# PCB.net
KiCad netlist of a schematic drawn in EasyEDA Pro
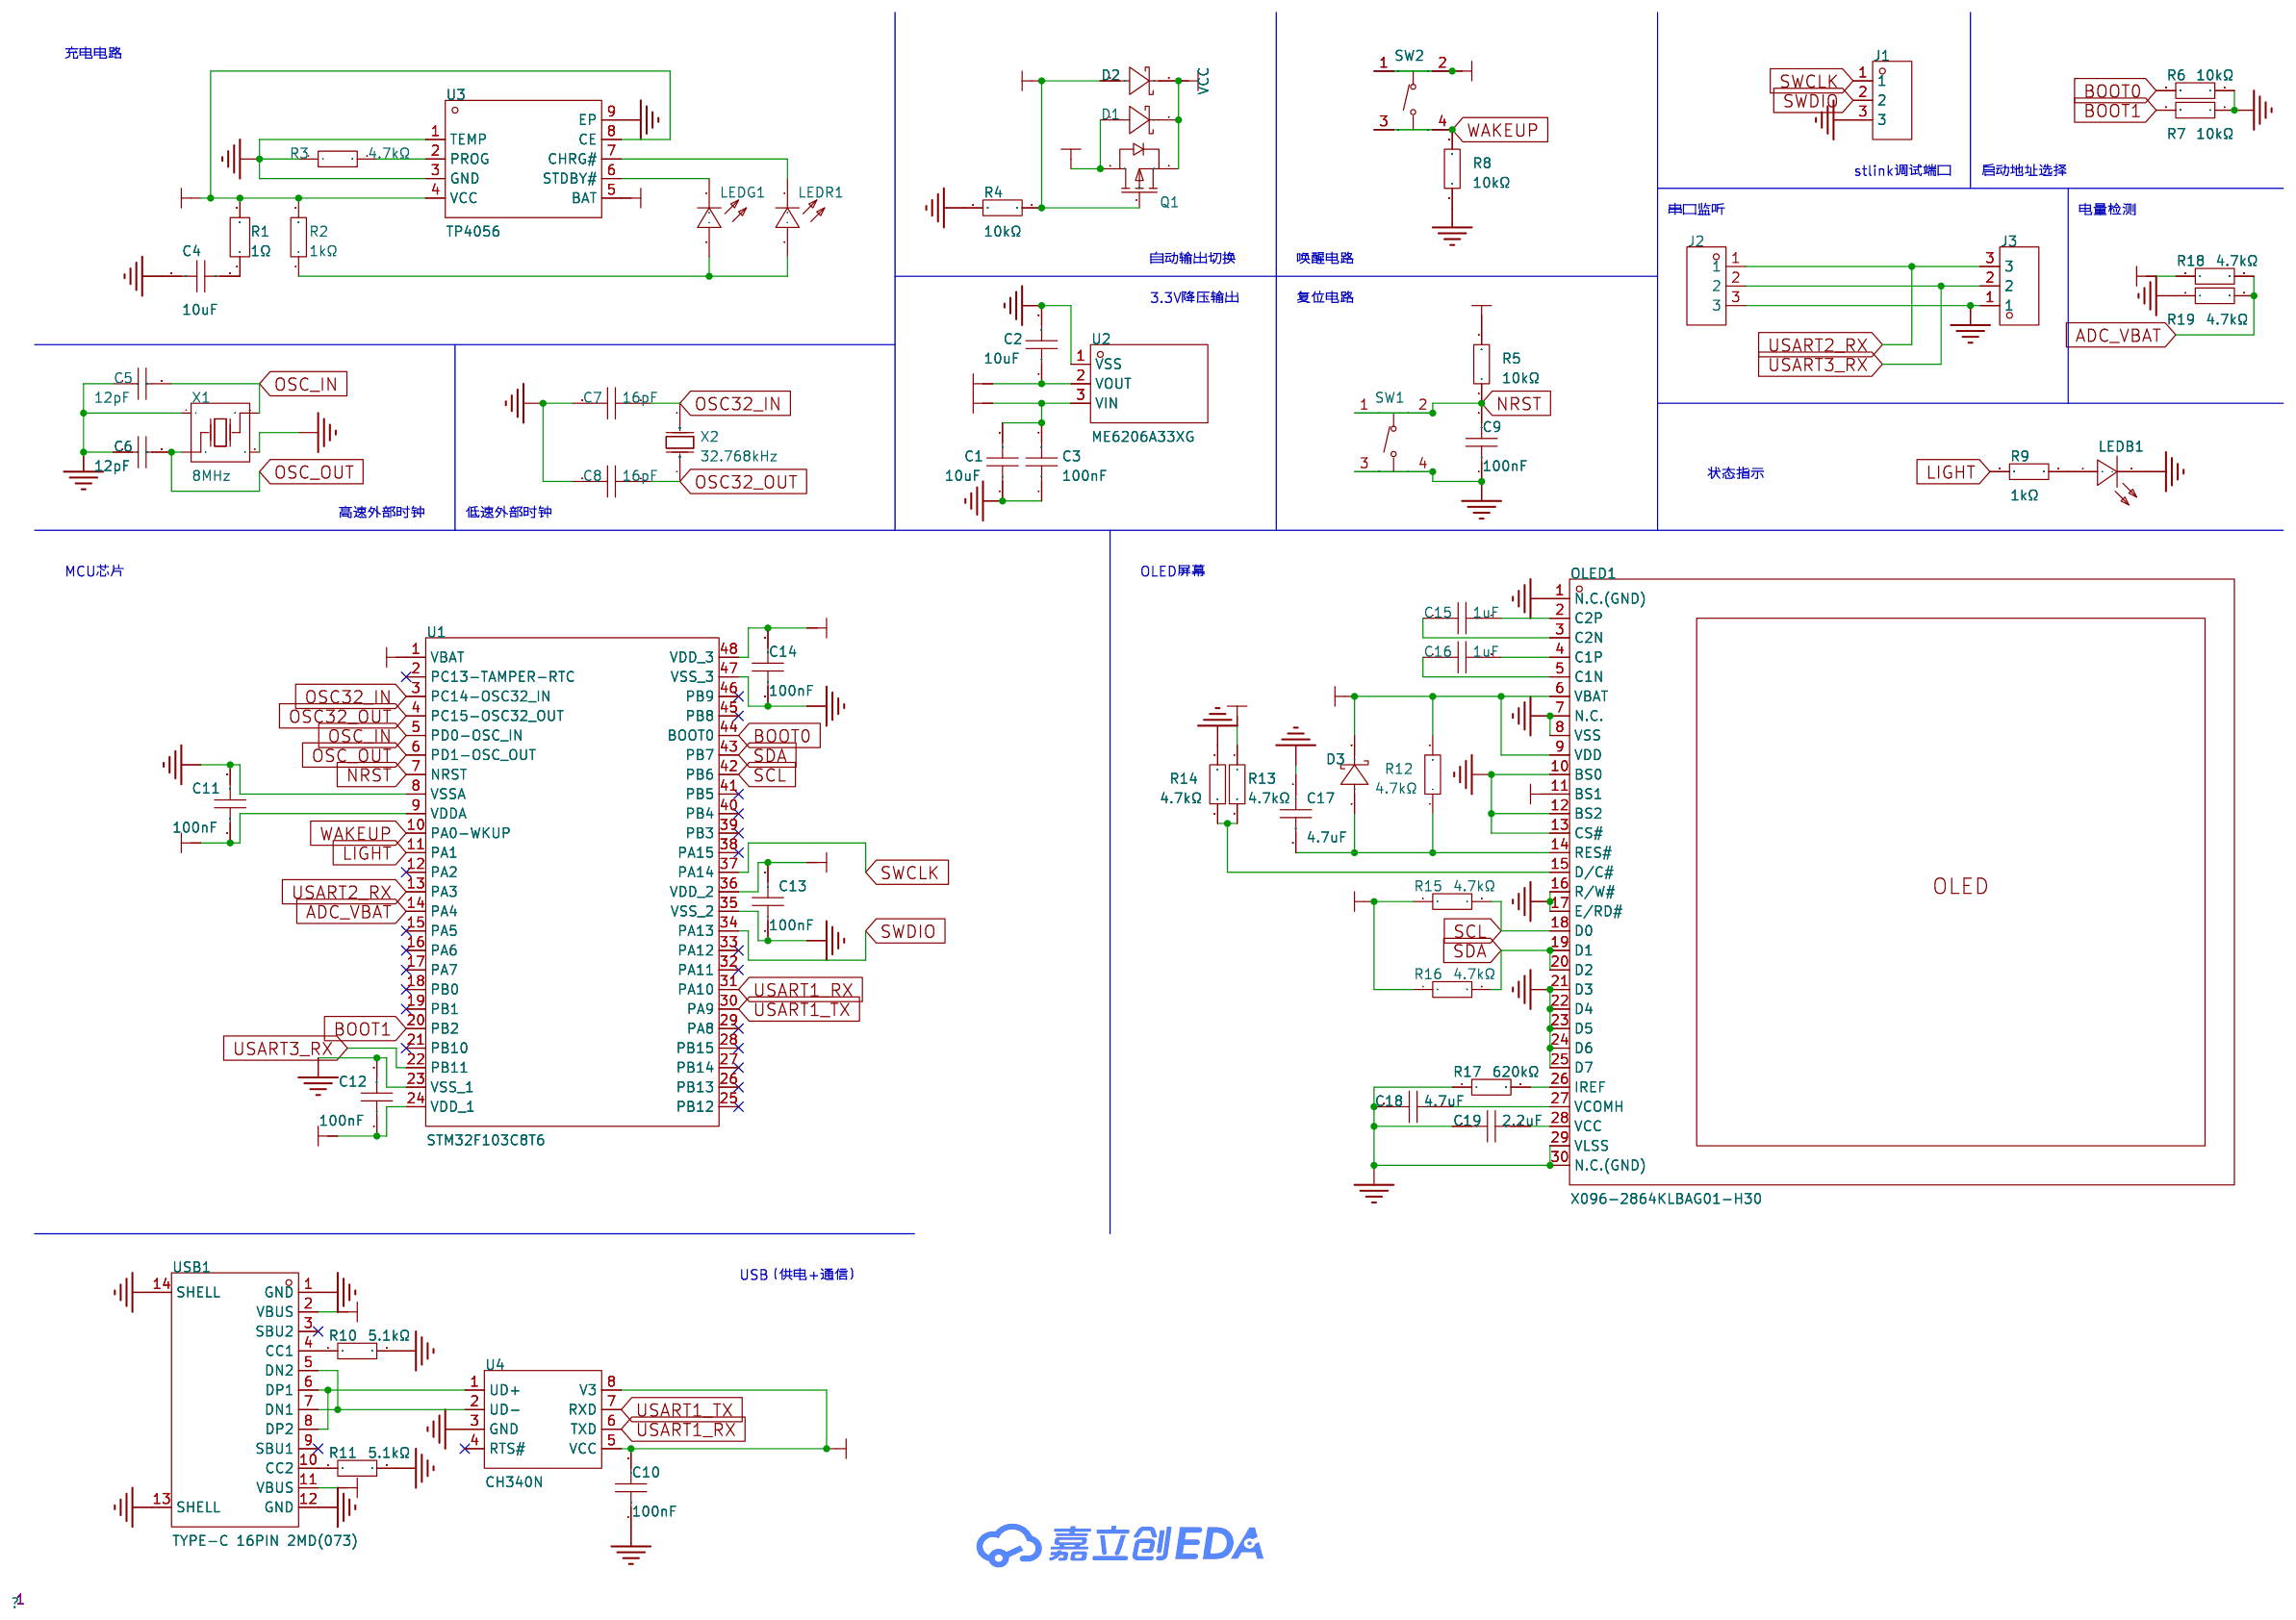
[diagram p0: schematic sheet]

(export (version "E")
  (design (tool "Eeschema 10.0.6"))
  (components
    (comp (ref "C1")
      (value "10uF")
      (footprint "easyedapro:C0603")
      (description "容值:10uF;精度:±10%;额定电压:10V;材质(温度系数):X5R;")
      (fields
        (field (name "Manufacturer Part") "CL10A106KP8NNNC")
        (field (name "Manufacturer") "SAMSUNG(三星)")
      )
      (libsource (lib "easyedapro") (part "CL10A106KP8NNNC"))
    )
    (comp (ref "C2")
      (value "10uF")
      (footprint "easyedapro:C0603")
      (description "容值:10uF;精度:±10%;额定电压:10V;材质(温度系数):X5R;")
      (fields
        (field (name "Manufacturer Part") "CL10A106KP8NNNC")
        (field (name "Manufacturer") "SAMSUNG(三星)")
      )
      (libsource (lib "easyedapro") (part "CL10A106KP8NNNC"))
    )
    (comp (ref "C3")
      (value "100nF")
      (footprint "easyedapro:C0603")
      (description "容值:100nF;精度:±10%;额定电压:50V;温度系数:X7R;")
      (fields
        (field (name "Manufacturer Part") "CGA0603X7R104K500JT")
        (field (name "Manufacturer") "HRE(芯声)")
      )
      (libsource (lib "easyedapro") (part "CGA0603X7R104K500JT"))
    )
    (comp (ref "C4")
      (value "10uF")
      (footprint "easyedapro:C0603")
      (description "容值:10uF;精度:±10%;额定电压:10V;材质(温度系数):X5R;")
      (fields
        (field (name "Manufacturer Part") "CL10A106KP8NNNC")
        (field (name "Manufacturer") "SAMSUNG(三星)")
      )
      (libsource (lib "easyedapro") (part "CL10A106KP8NNNC"))
    )
    (comp (ref "C5")
      (value "12pF")
      (footprint "easyedapro:C0603")
      (description "容值:12pF;精度:±5%;额定电压:50V;材质(温度系数):C0G;")
      (fields
        (field (name "Manufacturer Part") "CL10C120JB8NNNC")
        (field (name "Manufacturer") "SAMSUNG(三星)")
      )
      (libsource (lib "easyedapro") (part "CL10C120JB8NNNC"))
    )
    (comp (ref "C6")
      (value "12pF")
      (footprint "easyedapro:C0603")
      (description "容值:12pF;精度:±5%;额定电压:50V;材质(温度系数):C0G;")
      (fields
        (field (name "Manufacturer Part") "CL10C120JB8NNNC")
        (field (name "Manufacturer") "SAMSUNG(三星)")
      )
      (libsource (lib "easyedapro") (part "CL10C120JB8NNNC"))
    )
    (comp (ref "C7")
      (value "16pF")
      (footprint "easyedapro:C0603")
      (description "容值:16pF;精度:±5%;额定电压:50V;材质(温度系数):NP0;")
      (fields
        (field (name "Manufacturer Part") "CC0603JRNPO9BN160")
        (field (name "Manufacturer") "YAGEO(国巨)")
      )
      (libsource (lib "easyedapro") (part "CC0603JRNPO9BN160"))
    )
    (comp (ref "C8")
      (value "16pF")
      (footprint "easyedapro:C0603")
      (description "容值:16pF;精度:±5%;额定电压:50V;材质(温度系数):NP0;")
      (fields
        (field (name "Manufacturer Part") "CC0603JRNPO9BN160")
        (field (name "Manufacturer") "YAGEO(国巨)")
      )
      (libsource (lib "easyedapro") (part "CC0603JRNPO9BN160"))
    )
    (comp (ref "C9")
      (value "100nF")
      (footprint "easyedapro:C0603")
      (description "容值:100nF;精度:±10%;额定电压:50V;温度系数:X7R;")
      (fields
        (field (name "Manufacturer Part") "CGA0603X7R104K500JT")
        (field (name "Manufacturer") "HRE(芯声)")
      )
      (libsource (lib "easyedapro") (part "CGA0603X7R104K500JT"))
    )
    (comp (ref "C10")
      (value "100nF")
      (footprint "easyedapro:C0603")
      (description "容值:100nF;精度:±10%;额定电压:50V;温度系数:X7R;")
      (fields
        (field (name "Manufacturer Part") "CGA0603X7R104K500JT")
        (field (name "Manufacturer") "HRE(芯声)")
      )
      (libsource (lib "easyedapro") (part "CGA0603X7R104K500JT"))
    )
    (comp (ref "C11")
      (value "100nF")
      (footprint "easyedapro:C0603")
      (description "容值:100nF;精度:±10%;额定电压:50V;温度系数:X7R;")
      (fields
        (field (name "Manufacturer Part") "CGA0603X7R104K500JT")
        (field (name "Manufacturer") "HRE(芯声)")
      )
      (libsource (lib "easyedapro") (part "CGA0603X7R104K500JT"))
    )
    (comp (ref "C12")
      (value "100nF")
      (footprint "easyedapro:C0603")
      (description "容值:100nF;精度:±10%;额定电压:50V;温度系数:X7R;")
      (fields
        (field (name "Manufacturer Part") "CGA0603X7R104K500JT")
        (field (name "Manufacturer") "HRE(芯声)")
      )
      (libsource (lib "easyedapro") (part "CGA0603X7R104K500JT"))
    )
    (comp (ref "C13")
      (value "100nF")
      (footprint "easyedapro:C0603")
      (description "容值:100nF;精度:±10%;额定电压:50V;温度系数:X7R;")
      (fields
        (field (name "Manufacturer Part") "CGA0603X7R104K500JT")
        (field (name "Manufacturer") "HRE(芯声)")
      )
      (libsource (lib "easyedapro") (part "CGA0603X7R104K500JT"))
    )
    (comp (ref "C14")
      (value "100nF")
      (footprint "easyedapro:C0603")
      (description "容值:100nF;精度:±10%;额定电压:50V;温度系数:X7R;")
      (fields
        (field (name "Manufacturer Part") "CGA0603X7R104K500JT")
        (field (name "Manufacturer") "HRE(芯声)")
      )
      (libsource (lib "easyedapro") (part "CGA0603X7R104K500JT"))
    )
    (comp (ref "C15")
      (value "1uF")
      (footprint "easyedapro:C0603")
      (description "容值:1uF;精度:±10%;额定电压:50V;材质(温度系数):X5R;")
      (fields
        (field (name "Manufacturer Part") "CL10A105KB8NNNC")
        (field (name "Manufacturer") "SAMSUNG(三星)")
      )
      (libsource (lib "easyedapro") (part "CL10A105KB8NNNC"))
    )
    (comp (ref "C16")
      (value "1uF")
      (footprint "easyedapro:C0603")
      (description "容值:1uF;精度:±10%;额定电压:50V;材质(温度系数):X5R;")
      (fields
        (field (name "Manufacturer Part") "CL10A105KB8NNNC")
        (field (name "Manufacturer") "SAMSUNG(三星)")
      )
      (libsource (lib "easyedapro") (part "CL10A105KB8NNNC"))
    )
    (comp (ref "C17")
      (value "4.7uF")
      (footprint "easyedapro:C0603")
      (description "容值:4.7uF;精度:±10%;额定电压:16V;材质(温度系数):X5R;")
      (fields
        (field (name "Manufacturer Part") "CL10A475KO8NNNC")
        (field (name "Manufacturer") "SAMSUNG(三星)")
      )
      (libsource (lib "easyedapro") (part "CL10A475KO8NNNC"))
    )
    (comp (ref "C18")
      (value "4.7uF")
      (footprint "easyedapro:C0603")
      (description "容值:4.7uF;精度:±10%;额定电压:16V;材质(温度系数):X5R;")
      (fields
        (field (name "Manufacturer Part") "CL10A475KO8NNNC")
        (field (name "Manufacturer") "SAMSUNG(三星)")
      )
      (libsource (lib "easyedapro") (part "CL10A475KO8NNNC"))
    )
    (comp (ref "C19")
      (value "2.2uF")
      (footprint "easyedapro:C0603")
      (description "容值:2.2uF;精度:±10%;额定电压:50V;材质(温度系数):X5R;")
      (fields
        (field (name "Manufacturer Part") "CL10A225KB8NNNC")
        (field (name "Manufacturer") "SAMSUNG(三星)")
      )
      (libsource (lib "easyedapro") (part "CL10A225KB8NNNC"))
    )
    (comp (ref "D1")
      (value "DSK14")
      (footprint "easyedapro:SOD-123_L2.8-W1.8-LS3.7-FD")
      (description "二极管配置:-;正向压降(Vf):550mV@1A;直流反向耐压(Vr):40V;平均整流电流(Io):1A;")
      (fields (field (name "Manufacturer") "FUXINSEMI(富芯森美)"))
      (libsource (lib "easyedapro") (part "DSK14_C908228"))
    )
    (comp (ref "D2")
      (value "DSK14")
      (footprint "easyedapro:SOD-123_L2.8-W1.8-LS3.7-FD")
      (description "二极管配置:-;正向压降(Vf):550mV@1A;直流反向耐压(Vr):40V;平均整流电流(Io):1A;")
      (fields (field (name "Manufacturer") "FUXINSEMI(富芯森美)"))
      (libsource (lib "easyedapro") (part "DSK14_C908228"))
    )
    (comp (ref "D3")
      (value "DSK14")
      (footprint "easyedapro:SOD-123_L2.8-W1.8-LS3.7-FD")
      (description "二极管配置:-;正向压降(Vf):550mV@1A;直流反向耐压(Vr):40V;平均整流电流(Io):1A;")
      (fields (field (name "Manufacturer") "FUXINSEMI(富芯森美)"))
      (libsource (lib "easyedapro") (part "DSK14_C908228"))
    )
    (comp (ref "J1")
      (value "X6511FRS-03-C85D30")
      (footprint "easyedapro:HDR-SMD_3P-P2.54-H-F-L11.5")
      (description "插孔结构:1x3P;间距:2.54mm;安装类型:卧贴;排数:单排;总孔位数:3P;塑高:8.5mm;")
      (fields (field (name "Manufacturer") "XKB Connectivity(中国星坤)"))
      (libsource (lib "easyedapro") (part "X6511FRS-03-C85D30"))
    )
    (comp (ref "J2")
      (value "X6511FRS-03-C85D30")
      (footprint "easyedapro:HDR-SMD_3P-P2.54-H-F-L11.5")
      (description "插孔结构:1x3P;间距:2.54mm;安装类型:卧贴;排数:单排;总孔位数:3P;塑高:8.5mm;")
      (fields (field (name "Manufacturer") "XKB Connectivity(中国星坤)"))
      (libsource (lib "easyedapro") (part "X6511FRS-03-C85D30"))
    )
    (comp (ref "J3")
      (value "X6511FRS-03-C85D30")
      (footprint "easyedapro:HDR-SMD_3P-P2.54-H-F-L11.5")
      (description "插孔结构:1x3P;间距:2.54mm;安装类型:卧贴;排数:单排;总孔位数:3P;塑高:8.5mm;")
      (fields (field (name "Manufacturer") "XKB Connectivity(中国星坤)"))
      (libsource (lib "easyedapro") (part "X6511FRS-03-C85D30"))
    )
    (comp (ref "LEDB1")
      (value "NCD0805B2")
      (footprint "easyedapro:LED0805-R-RD")
      (fields (field (name "Manufacturer") "国星光电"))
      (libsource (lib "easyedapro") (part "FC-A2012BK-470H2"))
    )
    (comp (ref "LEDG1")
      (value "NCD0603G1")
      (footprint "easyedapro:LED0603-RD_1")
      (fields (field (name "Manufacturer") "国星光电"))
      (libsource (lib "easyedapro") (part "FC-D1608UGK-520D10"))
    )
    (comp (ref "LEDR1")
      (value "NCD0603R1")
      (footprint "easyedapro:LED0603-RD_RED")
      (fields (field (name "Manufacturer") "国星光电"))
      (libsource (lib "easyedapro") (part "FC-DA1608HRK-620D"))
    )
    (comp (ref "OLED1")
      (value "X096-2864KLBAG01-H30")
      (footprint "easyedapro:OLED-SMD_X096-2864KLBAG01-H30")
      (description "主控芯片:SSD1315;尺寸(inch):0.96;像素分辨率:128x64;")
      (fields (field (name "Manufacturer") "Newvision(新智景)"))
      (libsource (lib "easyedapro") (part "X096-2864KLBAG01-H30"))
    )
    (comp (ref "Q1")
      (value "SI2301S")
      (footprint "easyedapro:SOT-23-3_L2.9-W1.3-P0.95-LS2.4-BR")
      (description "类型:-;漏源电压(Vdss):20V;连续漏极电流(Id):2.3A;导通电阻(RDS(on)):142mΩ@2.5V,2A;耗散功率(Pd):-;阈值电压(Vgs(th)):400mV;")
      (fields (field (name "Manufacturer") "GOODWORK(固得沃克)"))
      (libsource (lib "easyedapro") (part "SI2301S_C18186231"))
    )
    (comp (ref "R1")
      (value "1Ω")
      (footprint "easyedapro:R0603")
      (description "电阻类型:厚膜电阻;阻值:1Ω;精度:±5%;功率:100mW;最大工作电压:75V;温度系数:±200ppm/°C;")
      (fields (field (name "Manufacturer Part") "FRC0603J1R0 TS") (field (name "Manufacturer") "FOJAN(富捷)"))
      (libsource (lib "easyedapro") (part "FRC0603J1R0 TS"))
    )
    (comp (ref "R2")
      (value "1kΩ")
      (footprint "easyedapro:R0603")
      (description "电阻类型:厚膜电阻;阻值:1kΩ;精度:±1%;功率:100mW;最大工作电压:75V;温度系数:±100ppm/°C;")
      (fields
        (field (name "Manufacturer Part") "0603WAF1001T5E")
        (field (name "Manufacturer") "UNI-ROYAL(厚声)")
      )
      (libsource (lib "easyedapro") (part "0603WAF1001T5E"))
    )
    (comp (ref "R3")
      (value "4.7kΩ")
      (footprint "easyedapro:R0603")
      (description "电阻类型:厚膜电阻;阻值:4.7kΩ;精度:±1%;功率:100mW;最大工作电压:75V;温度系数:±100ppm/°C;")
      (fields
        (field (name "Manufacturer Part") "0603WAF4701T5E")
        (field (name "Manufacturer") "UNI-ROYAL(厚声)")
      )
      (libsource (lib "easyedapro") (part "0603WAF4701T5E"))
    )
    (comp (ref "R4")
      (value "10kΩ")
      (footprint "easyedapro:R0603")
      (description "电阻类型:厚膜电阻;阻值:10kΩ;精度:±1%;功率:100mW;最大工作电压:75V;温度系数:±100ppm/°C;")
      (fields
        (field (name "Manufacturer Part") "0603WAF1002T5E")
        (field (name "Manufacturer") "UNI-ROYAL(厚声)")
      )
      (libsource (lib "easyedapro") (part "0603WAF1002T5E"))
    )
    (comp (ref "R5")
      (value "10kΩ")
      (footprint "easyedapro:R0603")
      (description "电阻类型:厚膜电阻;阻值:10kΩ;精度:±1%;功率:100mW;最大工作电压:75V;温度系数:±100ppm/°C;")
      (fields
        (field (name "Manufacturer Part") "0603WAF1002T5E")
        (field (name "Manufacturer") "UNI-ROYAL(厚声)")
      )
      (libsource (lib "easyedapro") (part "0603WAF1002T5E"))
    )
    (comp (ref "R6")
      (value "10kΩ")
      (footprint "easyedapro:R0603")
      (description "电阻类型:厚膜电阻;阻值:10kΩ;精度:±1%;功率:100mW;最大工作电压:75V;温度系数:±100ppm/°C;")
      (fields
        (field (name "Manufacturer Part") "0603WAF1002T5E")
        (field (name "Manufacturer") "UNI-ROYAL(厚声)")
      )
      (libsource (lib "easyedapro") (part "0603WAF1002T5E"))
    )
    (comp (ref "R7")
      (value "10kΩ")
      (footprint "easyedapro:R0603")
      (description "电阻类型:厚膜电阻;阻值:10kΩ;精度:±1%;功率:100mW;最大工作电压:75V;温度系数:±100ppm/°C;")
      (fields
        (field (name "Manufacturer Part") "0603WAF1002T5E")
        (field (name "Manufacturer") "UNI-ROYAL(厚声)")
      )
      (libsource (lib "easyedapro") (part "0603WAF1002T5E"))
    )
    (comp (ref "R8")
      (value "10kΩ")
      (footprint "easyedapro:R0603")
      (description "电阻类型:厚膜电阻;阻值:10kΩ;精度:±1%;功率:100mW;最大工作电压:75V;温度系数:±100ppm/°C;")
      (fields
        (field (name "Manufacturer Part") "0603WAF1002T5E")
        (field (name "Manufacturer") "UNI-ROYAL(厚声)")
      )
      (libsource (lib "easyedapro") (part "0603WAF1002T5E"))
    )
    (comp (ref "R9")
      (value "1kΩ")
      (footprint "easyedapro:R0603")
      (description "电阻类型:厚膜电阻;阻值:1kΩ;精度:±1%;功率:100mW;最大工作电压:75V;温度系数:±100ppm/°C;")
      (fields
        (field (name "Manufacturer Part") "0603WAF1001T5E")
        (field (name "Manufacturer") "UNI-ROYAL(厚声)")
      )
      (libsource (lib "easyedapro") (part "0603WAF1001T5E"))
    )
    (comp (ref "R10")
      (value "5.1kΩ")
      (footprint "easyedapro:R0603")
      (description "阻值:5.1kΩ;精度:±1%;功率:100mW;")
      (fields (field (name "Manufacturer Part") "ETCR0603F5K10K9") (field (name "Manufacturer") "RESI(开步睿思)"))
      (libsource (lib "easyedapro") (part "ETCR0603F5K10K9"))
    )
    (comp (ref "R11")
      (value "5.1kΩ")
      (footprint "easyedapro:R0603")
      (description "阻值:5.1kΩ;精度:±1%;功率:100mW;")
      (fields (field (name "Manufacturer Part") "ETCR0603F5K10K9") (field (name "Manufacturer") "RESI(开步睿思)"))
      (libsource (lib "easyedapro") (part "ETCR0603F5K10K9"))
    )
    (comp (ref "R12")
      (value "4.7kΩ")
      (footprint "easyedapro:R0603")
      (description "电阻类型:厚膜电阻;阻值:4.7kΩ;精度:±1%;功率:100mW;最大工作电压:75V;温度系数:±100ppm/°C;")
      (fields
        (field (name "Manufacturer Part") "0603WAF4701T5E")
        (field (name "Manufacturer") "UNI-ROYAL(厚声)")
      )
      (libsource (lib "easyedapro") (part "0603WAF4701T5E"))
    )
    (comp (ref "R13")
      (value "4.7kΩ")
      (footprint "easyedapro:R0603")
      (description "电阻类型:厚膜电阻;阻值:4.7kΩ;精度:±1%;功率:100mW;最大工作电压:75V;温度系数:±100ppm/°C;")
      (fields
        (field (name "Manufacturer Part") "0603WAF4701T5E")
        (field (name "Manufacturer") "UNI-ROYAL(厚声)")
      )
      (libsource (lib "easyedapro") (part "0603WAF4701T5E"))
    )
    (comp (ref "R14")
      (value "4.7kΩ")
      (footprint "easyedapro:R0603")
      (description "电阻类型:厚膜电阻;阻值:4.7kΩ;精度:±1%;功率:100mW;最大工作电压:75V;温度系数:±100ppm/°C;")
      (fields
        (field (name "Manufacturer Part") "0603WAF4701T5E")
        (field (name "Manufacturer") "UNI-ROYAL(厚声)")
      )
      (libsource (lib "easyedapro") (part "0603WAF4701T5E"))
    )
    (comp (ref "R15")
      (value "4.7kΩ")
      (footprint "easyedapro:R0603")
      (description "电阻类型:厚膜电阻;阻值:4.7kΩ;精度:±1%;功率:100mW;最大工作电压:75V;温度系数:±100ppm/°C;")
      (fields
        (field (name "Manufacturer Part") "0603WAF4701T5E")
        (field (name "Manufacturer") "UNI-ROYAL(厚声)")
      )
      (libsource (lib "easyedapro") (part "0603WAF4701T5E"))
    )
    (comp (ref "R16")
      (value "4.7kΩ")
      (footprint "easyedapro:R0603")
      (description "电阻类型:厚膜电阻;阻值:4.7kΩ;精度:±1%;功率:100mW;最大工作电压:75V;温度系数:±100ppm/°C;")
      (fields
        (field (name "Manufacturer Part") "0603WAF4701T5E")
        (field (name "Manufacturer") "UNI-ROYAL(厚声)")
      )
      (libsource (lib "easyedapro") (part "0603WAF4701T5E"))
    )
    (comp (ref "R17")
      (value "620kΩ")
      (footprint "easyedapro:R0603")
      (description "电阻类型:厚膜电阻;阻值:620kΩ;精度:±1%;功率:100mW;最大工作电压:75V;温度系数:±100ppm/°C;")
      (fields
        (field (name "Manufacturer Part") "0603WAF6203T5E")
        (field (name "Manufacturer") "UNI-ROYAL(厚声)")
      )
      (libsource (lib "easyedapro") (part "0603WAF6203T5E"))
    )
    (comp (ref "R18")
      (value "4.7kΩ")
      (footprint "easyedapro:R0603")
      (description "电阻类型:厚膜电阻;阻值:4.7kΩ;精度:±1%;功率:100mW;最大工作电压:75V;温度系数:±100ppm/°C;")
      (fields
        (field (name "Manufacturer Part") "0603WAF4701T5E")
        (field (name "Manufacturer") "UNI-ROYAL(厚声)")
      )
      (libsource (lib "easyedapro") (part "0603WAF4701T5E"))
    )
    (comp (ref "R19")
      (value "4.7kΩ")
      (footprint "easyedapro:R0603")
      (description "电阻类型:厚膜电阻;阻值:4.7kΩ;精度:±1%;功率:100mW;最大工作电压:75V;温度系数:±100ppm/°C;")
      (fields
        (field (name "Manufacturer Part") "0603WAF4701T5E")
        (field (name "Manufacturer") "UNI-ROYAL(厚声)")
      )
      (libsource (lib "easyedapro") (part "0603WAF4701T5E"))
    )
    (comp (ref "SW1")
      (value "TS-1187A-B-A-B")
      (footprint "easyedapro:SW-SMD_4P-L5.1-W5.1-P3.70-LS6.5-TL_H1.5")
      (fields (field (name "Manufacturer") "XKB Connectivity(中国星坤)"))
      (libsource (lib "easyedapro") (part "TS-1187A-B-A-B"))
    )
    (comp (ref "SW2")
      (value "TS-1187A-B-A-B")
      (footprint "easyedapro:SW-SMD_4P-L5.1-W5.1-P3.70-LS6.5-TL_H1.5")
      (fields (field (name "Manufacturer") "XKB Connectivity(中国星坤)"))
      (libsource (lib "easyedapro") (part "TS-1187A-B-A-B"))
    )
    (comp (ref "U1")
      (value "STM32F103C8T6")
      (footprint "easyedapro:LQFP-48_L7.0-W7.0-P0.50-LS9.0-BL")
      (description "CPU内核:ARM-M3;CPU最大主频:72MHz;应用领域:-;")
      (fields (field (name "Manufacturer") "ST(意法半导体)"))
      (libsource (lib "easyedapro") (part "STM32F103C8T6"))
    )
    (comp (ref "U2")
      (value "ME6206A33XG")
      (footprint "easyedapro:SOT-23-3_L2.9-W1.6-P1.90-LS2.8-BR")
      (description "输出类型:固定;最大输入电压:6V;输出电压:3.3V;最大输出电流:300mA;电源纹波抑制比(PSRR):50dB@(1kHz);输出极性:正极;")
      (fields (field (name "Manufacturer") "MICRONE(南京微盟)"))
      (libsource (lib "easyedapro") (part "ME6206A33XG"))
    )
    (comp (ref "U3")
      (value "TP4056")
      (footprint "easyedapro:ESOP-8_L4.9-W3.9-P1.27-LS6.0-BL-EP")
      (description "工作电压:4V~6V;最大充电电流:1A;电池类型:锂离子/聚合物;电池节数:1;")
      (fields (field (name "Manufacturer") "TPOWER(天源)"))
      (libsource (lib "easyedapro") (part "TP4056_C382139"))
    )
    (comp (ref "U4")
      (value "CH340N")
      (footprint "easyedapro:SOP-8_L4.9-W3.9-P1.27-LS6.0-BL")
      (description "应用功能:USB转串口;接口协议:USB 2.0;通道数:1;数据速率:2Mbps;")
      (fields (field (name "Manufacturer") "WCH(南京沁恒)"))
      (libsource (lib "easyedapro") (part "CH340N_C2977777"))
    )
    (comp (ref "USB1")
      (value "TYPE-C 16PIN 2MD(073)")
      (footprint "easyedapro:USB-C-SMD_TYPE-C-6PIN-2MD-073")
      (description "连接器类型:Type-C;标准:USB 3.1;公母:母;安装方式:卧贴;触点数量:16P;端口数量:1;额定电流 - 电源:5A;工作温度范围:-25°C~+85°C;")
      (fields (field (name "Manufacturer") "SHOU HAN(首韩)"))
      (libsource (lib "easyedapro") (part "TYPE-C 16PIN 2MD(073)"))
    )
    (comp (ref "X1")
      (value "8MHz")
      (footprint "easyedapro:CRYSTAL-SMD_4P-L3.2-W2.5-BL")
      (description "晶振类型:贴片晶振;频率:8MHz;常温频差:±10ppm;负载电容:10pF;频率稳定度:±15ppm;")
      (fields (field (name "Manufacturer Part") "TAXM8M4RDBCCT2T") (field (name "Manufacturer") "YJX(雅晶鑫)"))
      (libsource (lib "easyedapro") (part "TAXM8M4RDBCCT2T"))
    )
    (comp (ref "X2")
      (value "32.768kHz")
      (footprint "easyedapro:CRYSTAL-SMD_L3.2-W1.5-1")
      (description "晶振类型:贴片晶振;频率:32.768kHz;常温频差:±20ppm;负载电容:12.5pF;频率稳定度:±30ppm;")
      (fields
        (field (name "Manufacturer Part") "XKXGI-SUA-32.768K")
        (field (name "Manufacturer") "YXC(扬兴晶振)")
      )
      (libsource (lib "easyedapro") (part "XKXGI-SUA-32.768K"))
    )
  )
  (nets
    (net (code "1") (name "3V3") (class "Default")
      (node (ref "C10") (pin "2") (pinfunction "2_2") (pintype "unspecified"))
      (node (ref "C11") (pin "1") (pinfunction "1_1") (pintype "unspecified"))
      (node (ref "C12") (pin "1") (pinfunction "1_1") (pintype "unspecified"))
      (node (ref "C13") (pin "2") (pinfunction "2_2") (pintype "unspecified"))
      (node (ref "C14") (pin "2") (pinfunction "2_2") (pintype "unspecified"))
      (node (ref "C2") (pin "1") (pinfunction "1_1") (pintype "unspecified"))
      (node (ref "D3") (pin "2") (pinfunction "K_2") (pintype "unspecified"))
      (node (ref "OLED1") (pin "11") (pinfunction "BS1_11") (pintype "unspecified"))
      (node (ref "OLED1") (pin "6") (pinfunction "VBAT_6") (pintype "unspecified"))
      (node (ref "OLED1") (pin "9") (pinfunction "VDD_9") (pintype "unspecified"))
      (node (ref "R12") (pin "2") (pinfunction "2_2") (pintype "input"))
      (node (ref "R13") (pin "1") (pinfunction "1_1") (pintype "input"))
      (node (ref "R15") (pin "1") (pinfunction "1_1") (pintype "input"))
      (node (ref "R16") (pin "1") (pinfunction "1_1") (pintype "input"))
      (node (ref "R5") (pin "2") (pinfunction "2_2") (pintype "input"))
      (node (ref "SW2") (pin "1") (pinfunction "A_1") (pintype "unspecified"))
      (node (ref "SW2") (pin "2") (pinfunction "B_2") (pintype "unspecified"))
      (node (ref "U1") (pin "1") (pinfunction "VBAT_1") (pintype "unspecified"))
      (node (ref "U1") (pin "24") (pinfunction "VDD_1_24") (pintype "unspecified"))
      (node (ref "U1") (pin "36") (pinfunction "VDD_2_36") (pintype "unspecified"))
      (node (ref "U1") (pin "48") (pinfunction "VDD_3_48") (pintype "unspecified"))
      (node (ref "U1") (pin "9") (pinfunction "VDDA_9") (pintype "unspecified"))
      (node (ref "U2") (pin "2") (pinfunction "VOUT_2") (pintype "unspecified"))
      (node (ref "U4") (pin "5") (pinfunction "VCC_5") (pintype "unspecified"))
      (node (ref "U4") (pin "8") (pinfunction "V3_8") (pintype "unspecified"))
    )
    (net (code "2") (name "5V") (class "Default")
      (node (ref "D2") (pin "1") (pinfunction "A_1") (pintype "unspecified"))
      (node (ref "Q1") (pin "1") (pinfunction "G_1") (pintype "unspecified"))
      (node (ref "R1") (pin "2") (pinfunction "2_2") (pintype "unspecified"))
      (node (ref "R2") (pin "2") (pinfunction "2_2") (pintype "input"))
      (node (ref "R4") (pin "1") (pinfunction "1_1") (pintype "input"))
      (node (ref "U3") (pin "4") (pinfunction "VCC_4") (pintype "unspecified"))
      (node (ref "U3") (pin "8") (pinfunction "CE_8") (pintype "unspecified"))
      (node (ref "USB1") (pin "11") (pinfunction "VBUS_11") (pintype "unspecified"))
      (node (ref "USB1") (pin "2") (pinfunction "VBUS_2") (pintype "unspecified"))
    )
    (net (code "3") (name "ADC_VBAT") (class "Default")
      (node (ref "R18") (pin "2") (pinfunction "2_2") (pintype "input"))
      (node (ref "R19") (pin "2") (pinfunction "2_2") (pintype "input"))
      (node (ref "U1") (pin "14") (pinfunction "PA4_14") (pintype "unspecified"))
    )
    (net (code "4") (name "BOOT0") (class "Default")
      (node (ref "R6") (pin "2") (pinfunction "2_2") (pintype "input"))
      (node (ref "U1") (pin "44") (pinfunction "BOOT0_44") (pintype "unspecified"))
    )
    (net (code "5") (name "BOOT1") (class "Default")
      (node (ref "R7") (pin "2") (pinfunction "2_2") (pintype "input"))
      (node (ref "U1") (pin "20") (pinfunction "PB2_20") (pintype "unspecified"))
    )
    (net (code "6") (name "GND") (class "Default")
      (node (ref "C1") (pin "1") (pinfunction "1_1") (pintype "unspecified"))
      (node (ref "C10") (pin "1") (pinfunction "1_1") (pintype "unspecified"))
      (node (ref "C11") (pin "2") (pinfunction "2_2") (pintype "unspecified"))
      (node (ref "C12") (pin "2") (pinfunction "2_2") (pintype "unspecified"))
      (node (ref "C13") (pin "1") (pinfunction "1_1") (pintype "unspecified"))
      (node (ref "C14") (pin "1") (pinfunction "1_1") (pintype "unspecified"))
      (node (ref "C17") (pin "1") (pinfunction "1_1") (pintype "unspecified"))
      (node (ref "C18") (pin "2") (pinfunction "2_2") (pintype "unspecified"))
      (node (ref "C19") (pin "1") (pinfunction "1_1") (pintype "unspecified"))
      (node (ref "C2") (pin "2") (pinfunction "2_2") (pintype "unspecified"))
      (node (ref "C3") (pin "1") (pinfunction "1_1") (pintype "unspecified"))
      (node (ref "C4") (pin "2") (pinfunction "2_2") (pintype "unspecified"))
      (node (ref "C5") (pin "1") (pinfunction "1_1") (pintype "input"))
      (node (ref "C6") (pin "1") (pinfunction "1_1") (pintype "input"))
      (node (ref "C7") (pin "2") (pinfunction "2_2") (pintype "unspecified"))
      (node (ref "C8") (pin "2") (pinfunction "2_2") (pintype "unspecified"))
      (node (ref "C9") (pin "1") (pinfunction "1_1") (pintype "unspecified"))
      (node (ref "J1") (pin "3") (pinfunction "3_3") (pintype "unspecified"))
      (node (ref "J2") (pin "3") (pinfunction "3_3") (pintype "unspecified"))
      (node (ref "J3") (pin "1") (pinfunction "1_1") (pintype "unspecified"))
      (node (ref "LEDB1") (pin "2") (pinfunction "-_2") (pintype "unspecified"))
      (node (ref "OLED1") (pin "1") (pinfunction "N.C.(GND)_1") (pintype "unspecified"))
      (node (ref "OLED1") (pin "10") (pinfunction "BS0_10") (pintype "unspecified"))
      (node (ref "OLED1") (pin "12") (pinfunction "BS2_12") (pintype "unspecified"))
      (node (ref "OLED1") (pin "13") (pinfunction "CS#_13") (pintype "unspecified"))
      (node (ref "OLED1") (pin "16") (pinfunction "R/W#_16") (pintype "unspecified"))
      (node (ref "OLED1") (pin "17") (pinfunction "E/RD#_17") (pintype "unspecified"))
      (node (ref "OLED1") (pin "21") (pinfunction "D3_21") (pintype "unspecified"))
      (node (ref "OLED1") (pin "22") (pinfunction "D4_22") (pintype "unspecified"))
      (node (ref "OLED1") (pin "23") (pinfunction "D5_23") (pintype "unspecified"))
      (node (ref "OLED1") (pin "24") (pinfunction "D6_24") (pintype "unspecified"))
      (node (ref "OLED1") (pin "25") (pinfunction "D7_25") (pintype "unspecified"))
      (node (ref "OLED1") (pin "29") (pinfunction "VLSS_29") (pintype "unspecified"))
      (node (ref "OLED1") (pin "30") (pinfunction "N.C.(GND)_30") (pintype "unspecified"))
      (node (ref "OLED1") (pin "7") (pinfunction "N.C._7") (pintype "unspecified"))
      (node (ref "OLED1") (pin "8") (pinfunction "VSS_8") (pintype "unspecified"))
      (node (ref "R10") (pin "2") (pinfunction "2_2") (pintype "unspecified"))
      (node (ref "R11") (pin "2") (pinfunction "2_2") (pintype "unspecified"))
      (node (ref "R14") (pin "1") (pinfunction "1_1") (pintype "input"))
      (node (ref "R17") (pin "1") (pinfunction "1_1") (pintype "input"))
      (node (ref "R19") (pin "1") (pinfunction "1_1") (pintype "input"))
      (node (ref "R3") (pin "1") (pinfunction "1_1") (pintype "input"))
      (node (ref "R4") (pin "2") (pinfunction "2_2") (pintype "input"))
      (node (ref "R6") (pin "1") (pinfunction "1_1") (pintype "input"))
      (node (ref "R7") (pin "1") (pinfunction "1_1") (pintype "input"))
      (node (ref "R8") (pin "1") (pinfunction "1_1") (pintype "input"))
      (node (ref "SW1") (pin "3") (pinfunction "C_3") (pintype "unspecified"))
      (node (ref "SW1") (pin "4") (pinfunction "D_4") (pintype "unspecified"))
      (node (ref "U1") (pin "23") (pinfunction "VSS_1_23") (pintype "unspecified"))
      (node (ref "U1") (pin "35") (pinfunction "VSS_2_35") (pintype "unspecified"))
      (node (ref "U1") (pin "47") (pinfunction "VSS_3_47") (pintype "unspecified"))
      (node (ref "U1") (pin "8") (pinfunction "VSSA_8") (pintype "unspecified"))
      (node (ref "U2") (pin "1") (pinfunction "VSS_1") (pintype "unspecified"))
      (node (ref "U3") (pin "1") (pinfunction "TEMP_1") (pintype "unspecified"))
      (node (ref "U3") (pin "3") (pinfunction "GND_3") (pintype "unspecified"))
      (node (ref "U3") (pin "9") (pinfunction "EP_9") (pintype "unspecified"))
      (node (ref "U4") (pin "3") (pinfunction "GND_3") (pintype "unspecified"))
      (node (ref "USB1") (pin "1") (pinfunction "GND_1") (pintype "unspecified"))
      (node (ref "USB1") (pin "12") (pinfunction "GND_12") (pintype "unspecified"))
      (node (ref "USB1") (pin "13") (pinfunction "SHELL_13") (pintype "unspecified"))
      (node (ref "USB1") (pin "14") (pinfunction "SHELL_14") (pintype "unspecified"))
      (node (ref "X1") (pin "2") (pinfunction "2_2") (pintype "input"))
      (node (ref "X1") (pin "4") (pinfunction "4_4") (pintype "input"))
    )
    (net (code "7") (name "LIGHT") (class "Default")
      (node (ref "R9") (pin "2") (pinfunction "2_2") (pintype "input"))
      (node (ref "U1") (pin "11") (pinfunction "PA1_11") (pintype "unspecified"))
    )
    (net (code "8") (name "NRST") (class "Default")
      (node (ref "C9") (pin "2") (pinfunction "2_2") (pintype "unspecified"))
      (node (ref "R5") (pin "1") (pinfunction "1_1") (pintype "input"))
      (node (ref "SW1") (pin "1") (pinfunction "A_1") (pintype "unspecified"))
      (node (ref "SW1") (pin "2") (pinfunction "B_2") (pintype "unspecified"))
      (node (ref "U1") (pin "7") (pinfunction "NRST_7") (pintype "unspecified"))
    )
    (net (code "9") (name "Net-(C4-Pad1)") (class "Default")
      (node (ref "C4") (pin "1") (pinfunction "1_1") (pintype "unspecified"))
      (node (ref "R1") (pin "1") (pinfunction "1_1") (pintype "unspecified"))
    )
    (net (code "10") (name "Net-(D3-A)") (class "Default")
      (node (ref "C17") (pin "2") (pinfunction "2_2") (pintype "unspecified"))
      (node (ref "D3") (pin "1") (pinfunction "A_1") (pintype "unspecified"))
      (node (ref "OLED1") (pin "14") (pinfunction "RES#_14") (pintype "unspecified"))
      (node (ref "R12") (pin "1") (pinfunction "1_1") (pintype "input"))
    )
    (net (code "11") (name "Net-(LEDB1-+)") (class "Default")
      (node (ref "LEDB1") (pin "1") (pinfunction "+_1") (pintype "unspecified"))
      (node (ref "R9") (pin "1") (pinfunction "1_1") (pintype "input"))
    )
    (net (code "12") (name "Net-(LEDG1-A)") (class "Default")
      (node (ref "LEDG1") (pin "2") (pinfunction "A_2") (pintype "input"))
      (node (ref "LEDR1") (pin "2") (pinfunction "A_2") (pintype "input"))
      (node (ref "R2") (pin "1") (pinfunction "1_1") (pintype "input"))
    )
    (net (code "13") (name "Net-(LEDG1-K)") (class "Default")
      (node (ref "LEDG1") (pin "1") (pinfunction "K_1") (pintype "input"))
      (node (ref "U3") (pin "6") (pinfunction "STDBY#_6") (pintype "unspecified"))
    )
    (net (code "14") (name "Net-(LEDR1-K)") (class "Default")
      (node (ref "LEDR1") (pin "1") (pinfunction "K_1") (pintype "input"))
      (node (ref "U3") (pin "7") (pinfunction "CHRG#_7") (pintype "unspecified"))
    )
    (net (code "15") (name "Net-(OLED1-C1N)") (class "Default")
      (node (ref "C16") (pin "1") (pinfunction "1_1") (pintype "unspecified"))
      (node (ref "OLED1") (pin "5") (pinfunction "C1N_5") (pintype "unspecified"))
    )
    (net (code "16") (name "Net-(OLED1-C1P)") (class "Default")
      (node (ref "C16") (pin "2") (pinfunction "2_2") (pintype "unspecified"))
      (node (ref "OLED1") (pin "4") (pinfunction "C1P_4") (pintype "unspecified"))
    )
    (net (code "17") (name "Net-(OLED1-C2N)") (class "Default")
      (node (ref "C15") (pin "1") (pinfunction "1_1") (pintype "unspecified"))
      (node (ref "OLED1") (pin "3") (pinfunction "C2N_3") (pintype "unspecified"))
    )
    (net (code "18") (name "Net-(OLED1-C2P)") (class "Default")
      (node (ref "C15") (pin "2") (pinfunction "2_2") (pintype "unspecified"))
      (node (ref "OLED1") (pin "2") (pinfunction "C2P_2") (pintype "unspecified"))
    )
    (net (code "19") (name "Net-(OLED1-D{slash}C#)") (class "Default")
      (node (ref "OLED1") (pin "15") (pinfunction "D/C#_15") (pintype "unspecified"))
      (node (ref "R13") (pin "2") (pinfunction "2_2") (pintype "input"))
      (node (ref "R14") (pin "2") (pinfunction "2_2") (pintype "input"))
    )
    (net (code "20") (name "Net-(OLED1-IREF)") (class "Default")
      (node (ref "OLED1") (pin "26") (pinfunction "IREF_26") (pintype "unspecified"))
      (node (ref "R17") (pin "2") (pinfunction "2_2") (pintype "input"))
    )
    (net (code "21") (name "Net-(OLED1-VCC)") (class "Default")
      (node (ref "C19") (pin "2") (pinfunction "2_2") (pintype "unspecified"))
      (node (ref "OLED1") (pin "28") (pinfunction "VCC_28") (pintype "unspecified"))
    )
    (net (code "22") (name "Net-(OLED1-VCOMH)") (class "Default")
      (node (ref "C18") (pin "1") (pinfunction "1_1") (pintype "unspecified"))
      (node (ref "OLED1") (pin "27") (pinfunction "VCOMH_27") (pintype "unspecified"))
    )
    (net (code "23") (name "Net-(U3-PROG)") (class "Default")
      (node (ref "R3") (pin "2") (pinfunction "2_2") (pintype "input"))
      (node (ref "U3") (pin "2") (pinfunction "PROG_2") (pintype "unspecified"))
    )
    (net (code "24") (name "Net-(U4-UD+)") (class "Default")
      (node (ref "U4") (pin "1") (pinfunction "UD+_1") (pintype "unspecified"))
      (node (ref "USB1") (pin "6") (pinfunction "DP1_6") (pintype "unspecified"))
      (node (ref "USB1") (pin "8") (pinfunction "DP2_8") (pintype "unspecified"))
    )
    (net (code "25") (name "Net-(U4-UD-)") (class "Default")
      (node (ref "U4") (pin "2") (pinfunction "UD-_2") (pintype "unspecified"))
      (node (ref "USB1") (pin "5") (pinfunction "DN2_5") (pintype "unspecified"))
      (node (ref "USB1") (pin "7") (pinfunction "DN1_7") (pintype "unspecified"))
    )
    (net (code "26") (name "Net-(USB1-CC1)") (class "Default")
      (node (ref "R10") (pin "1") (pinfunction "1_1") (pintype "unspecified"))
      (node (ref "USB1") (pin "4") (pinfunction "CC1_4") (pintype "unspecified"))
    )
    (net (code "27") (name "Net-(USB1-CC2)") (class "Default")
      (node (ref "R11") (pin "1") (pinfunction "1_1") (pintype "unspecified"))
      (node (ref "USB1") (pin "10") (pinfunction "CC2_10") (pintype "unspecified"))
    )
    (net (code "28") (name "OSC32_IN") (class "Default")
      (node (ref "C7") (pin "1") (pinfunction "1_1") (pintype "unspecified"))
      (node (ref "U1") (pin "3") (pinfunction "PC14-OSC32_IN_3") (pintype "unspecified"))
      (node (ref "X2") (pin "2") (pinfunction "OSC2_2") (pintype "input"))
    )
    (net (code "29") (name "OSC32_OUT") (class "Default")
      (node (ref "C8") (pin "1") (pinfunction "1_1") (pintype "unspecified"))
      (node (ref "U1") (pin "4") (pinfunction "PC15-OSC32_OUT_4") (pintype "unspecified"))
      (node (ref "X2") (pin "1") (pinfunction "OSC1_1") (pintype "input"))
    )
    (net (code "30") (name "OSC_IN") (class "Default")
      (node (ref "C5") (pin "2") (pinfunction "2_2") (pintype "input"))
      (node (ref "U1") (pin "5") (pinfunction "PD0-OSC_IN_5") (pintype "unspecified"))
      (node (ref "X1") (pin "3") (pinfunction "3_3") (pintype "input"))
    )
    (net (code "31") (name "OSC_OUT") (class "Default")
      (node (ref "C6") (pin "2") (pinfunction "2_2") (pintype "input"))
      (node (ref "U1") (pin "6") (pinfunction "PD1-OSC_OUT_6") (pintype "unspecified"))
      (node (ref "X1") (pin "1") (pinfunction "1_1") (pintype "input"))
    )
    (net (code "32") (name "SCL") (class "Default")
      (node (ref "OLED1") (pin "18") (pinfunction "D0_18") (pintype "unspecified"))
      (node (ref "R15") (pin "2") (pinfunction "2_2") (pintype "input"))
      (node (ref "U1") (pin "42") (pinfunction "PB6_42") (pintype "unspecified"))
    )
    (net (code "33") (name "SDA") (class "Default")
      (node (ref "OLED1") (pin "19") (pinfunction "D1_19") (pintype "unspecified"))
      (node (ref "OLED1") (pin "20") (pinfunction "D2_20") (pintype "unspecified"))
      (node (ref "R16") (pin "2") (pinfunction "2_2") (pintype "input"))
      (node (ref "U1") (pin "43") (pinfunction "PB7_43") (pintype "unspecified"))
    )
    (net (code "34") (name "SWCLK") (class "Default")
      (node (ref "J1") (pin "1") (pinfunction "1_1") (pintype "unspecified"))
      (node (ref "U1") (pin "37") (pinfunction "PA14_37") (pintype "unspecified"))
    )
    (net (code "35") (name "SWDIO") (class "Default")
      (node (ref "J1") (pin "2") (pinfunction "2_2") (pintype "unspecified"))
      (node (ref "U1") (pin "34") (pinfunction "PA13_34") (pintype "unspecified"))
    )
    (net (code "36") (name "USART1_RX") (class "Default")
      (node (ref "U1") (pin "31") (pinfunction "PA10_31") (pintype "unspecified"))
      (node (ref "U4") (pin "6") (pinfunction "TXD_6") (pintype "unspecified"))
    )
    (net (code "37") (name "USART1_TX") (class "Default")
      (node (ref "U1") (pin "30") (pinfunction "PA9_30") (pintype "unspecified"))
      (node (ref "U4") (pin "7") (pinfunction "RXD_7") (pintype "unspecified"))
    )
    (net (code "38") (name "USART2_RX") (class "Default")
      (node (ref "J2") (pin "1") (pinfunction "1_1") (pintype "unspecified"))
      (node (ref "J3") (pin "3") (pinfunction "3_3") (pintype "unspecified"))
      (node (ref "U1") (pin "13") (pinfunction "PA3_13") (pintype "unspecified"))
    )
    (net (code "39") (name "USART3_RX") (class "Default")
      (node (ref "J2") (pin "2") (pinfunction "2_2") (pintype "unspecified"))
      (node (ref "J3") (pin "2") (pinfunction "2_2") (pintype "unspecified"))
      (node (ref "U1") (pin "22") (pinfunction "PB11_22") (pintype "unspecified"))
    )
    (net (code "40") (name "VCC") (class "Default")
      (node (ref "C1") (pin "2") (pinfunction "2_2") (pintype "unspecified"))
      (node (ref "C3") (pin "2") (pinfunction "2_2") (pintype "unspecified"))
      (node (ref "D1") (pin "2") (pinfunction "K_2") (pintype "unspecified"))
      (node (ref "D2") (pin "2") (pinfunction "K_2") (pintype "unspecified"))
      (node (ref "Q1") (pin "2") (pinfunction "S_2") (pintype "unspecified"))
      (node (ref "U2") (pin "3") (pinfunction "VIN_3") (pintype "unspecified"))
    )
    (net (code "41") (name "V_BAT") (class "Default")
      (node (ref "D1") (pin "1") (pinfunction "A_1") (pintype "unspecified"))
      (node (ref "Q1") (pin "3") (pinfunction "D_3") (pintype "unspecified"))
      (node (ref "R18") (pin "1") (pinfunction "1_1") (pintype "input"))
      (node (ref "U3") (pin "5") (pinfunction "BAT_5") (pintype "unspecified"))
    )
    (net (code "42") (name "WAKEUP") (class "Default")
      (node (ref "R8") (pin "2") (pinfunction "2_2") (pintype "input"))
      (node (ref "SW2") (pin "3") (pinfunction "C_3") (pintype "unspecified"))
      (node (ref "SW2") (pin "4") (pinfunction "D_4") (pintype "unspecified"))
      (node (ref "U1") (pin "10") (pinfunction "PA0-WKUP_10") (pintype "unspecified"))
    )
    (net (code "43") (name "unconnected-(U1-PA2-Pad12)") (class "Default")
      (node (ref "U1") (pin "12") (pinfunction "PA2_12") (pintype "unspecified+no_connect"))
    )
    (net (code "44") (name "unconnected-(U1-PA5-Pad15)") (class "Default")
      (node (ref "U1") (pin "15") (pinfunction "PA5_15") (pintype "unspecified+no_connect"))
    )
    (net (code "45") (name "unconnected-(U1-PA6-Pad16)") (class "Default")
      (node (ref "U1") (pin "16") (pinfunction "PA6_16") (pintype "unspecified+no_connect"))
    )
    (net (code "46") (name "unconnected-(U1-PA7-Pad17)") (class "Default")
      (node (ref "U1") (pin "17") (pinfunction "PA7_17") (pintype "unspecified+no_connect"))
    )
    (net (code "47") (name "unconnected-(U1-PA8-Pad29)") (class "Default")
      (node (ref "U1") (pin "29") (pinfunction "PA8_29") (pintype "unspecified+no_connect"))
    )
    (net (code "48") (name "unconnected-(U1-PA11-Pad32)") (class "Default")
      (node (ref "U1") (pin "32") (pinfunction "PA11_32") (pintype "unspecified+no_connect"))
    )
    (net (code "49") (name "unconnected-(U1-PA12-Pad33)") (class "Default")
      (node (ref "U1") (pin "33") (pinfunction "PA12_33") (pintype "unspecified+no_connect"))
    )
    (net (code "50") (name "unconnected-(U1-PA15-Pad38)") (class "Default")
      (node (ref "U1") (pin "38") (pinfunction "PA15_38") (pintype "unspecified+no_connect"))
    )
    (net (code "51") (name "unconnected-(U1-PB0-Pad18)") (class "Default")
      (node (ref "U1") (pin "18") (pinfunction "PB0_18") (pintype "unspecified+no_connect"))
    )
    (net (code "52") (name "unconnected-(U1-PB1-Pad19)") (class "Default")
      (node (ref "U1") (pin "19") (pinfunction "PB1_19") (pintype "unspecified+no_connect"))
    )
    (net (code "53") (name "unconnected-(U1-PB3-Pad39)") (class "Default")
      (node (ref "U1") (pin "39") (pinfunction "PB3_39") (pintype "unspecified+no_connect"))
    )
    (net (code "54") (name "unconnected-(U1-PB4-Pad40)") (class "Default")
      (node (ref "U1") (pin "40") (pinfunction "PB4_40") (pintype "unspecified+no_connect"))
    )
    (net (code "55") (name "unconnected-(U1-PB5-Pad41)") (class "Default")
      (node (ref "U1") (pin "41") (pinfunction "PB5_41") (pintype "unspecified+no_connect"))
    )
    (net (code "56") (name "unconnected-(U1-PB8-Pad45)") (class "Default")
      (node (ref "U1") (pin "45") (pinfunction "PB8_45") (pintype "unspecified+no_connect"))
    )
    (net (code "57") (name "unconnected-(U1-PB9-Pad46)") (class "Default")
      (node (ref "U1") (pin "46") (pinfunction "PB9_46") (pintype "unspecified+no_connect"))
    )
    (net (code "58") (name "unconnected-(U1-PB10-Pad21)") (class "Default")
      (node (ref "U1") (pin "21") (pinfunction "PB10_21") (pintype "unspecified+no_connect"))
    )
    (net (code "59") (name "unconnected-(U1-PB12-Pad25)") (class "Default")
      (node (ref "U1") (pin "25") (pinfunction "PB12_25") (pintype "unspecified+no_connect"))
    )
    (net (code "60") (name "unconnected-(U1-PB13-Pad26)") (class "Default")
      (node (ref "U1") (pin "26") (pinfunction "PB13_26") (pintype "unspecified+no_connect"))
    )
    (net (code "61") (name "unconnected-(U1-PB14-Pad27)") (class "Default")
      (node (ref "U1") (pin "27") (pinfunction "PB14_27") (pintype "unspecified+no_connect"))
    )
    (net (code "62") (name "unconnected-(U1-PB15-Pad28)") (class "Default")
      (node (ref "U1") (pin "28") (pinfunction "PB15_28") (pintype "unspecified+no_connect"))
    )
    (net (code "63") (name "unconnected-(U1-PC13-TAMPER-RTC-Pad2)") (class "Default")
      (node (ref "U1") (pin "2") (pinfunction "PC13-TAMPER-RTC_2") (pintype "unspecified+no_connect"))
    )
    (net (code "64") (name "unconnected-(U4-RTS#-Pad4)") (class "Default")
      (node (ref "U4") (pin "4") (pinfunction "RTS#_4") (pintype "unspecified+no_connect"))
    )
    (net (code "65") (name "unconnected-(USB1-SBU1-Pad9)") (class "Default")
      (node (ref "USB1") (pin "9") (pinfunction "SBU1_9") (pintype "unspecified+no_connect"))
    )
    (net (code "66") (name "unconnected-(USB1-SBU2-Pad3)") (class "Default")
      (node (ref "USB1") (pin "3") (pinfunction "SBU2_3") (pintype "unspecified+no_connect"))
    )
  )
)
